# boot.net
KiCad netlist of a schematic drawn in Altium Designer
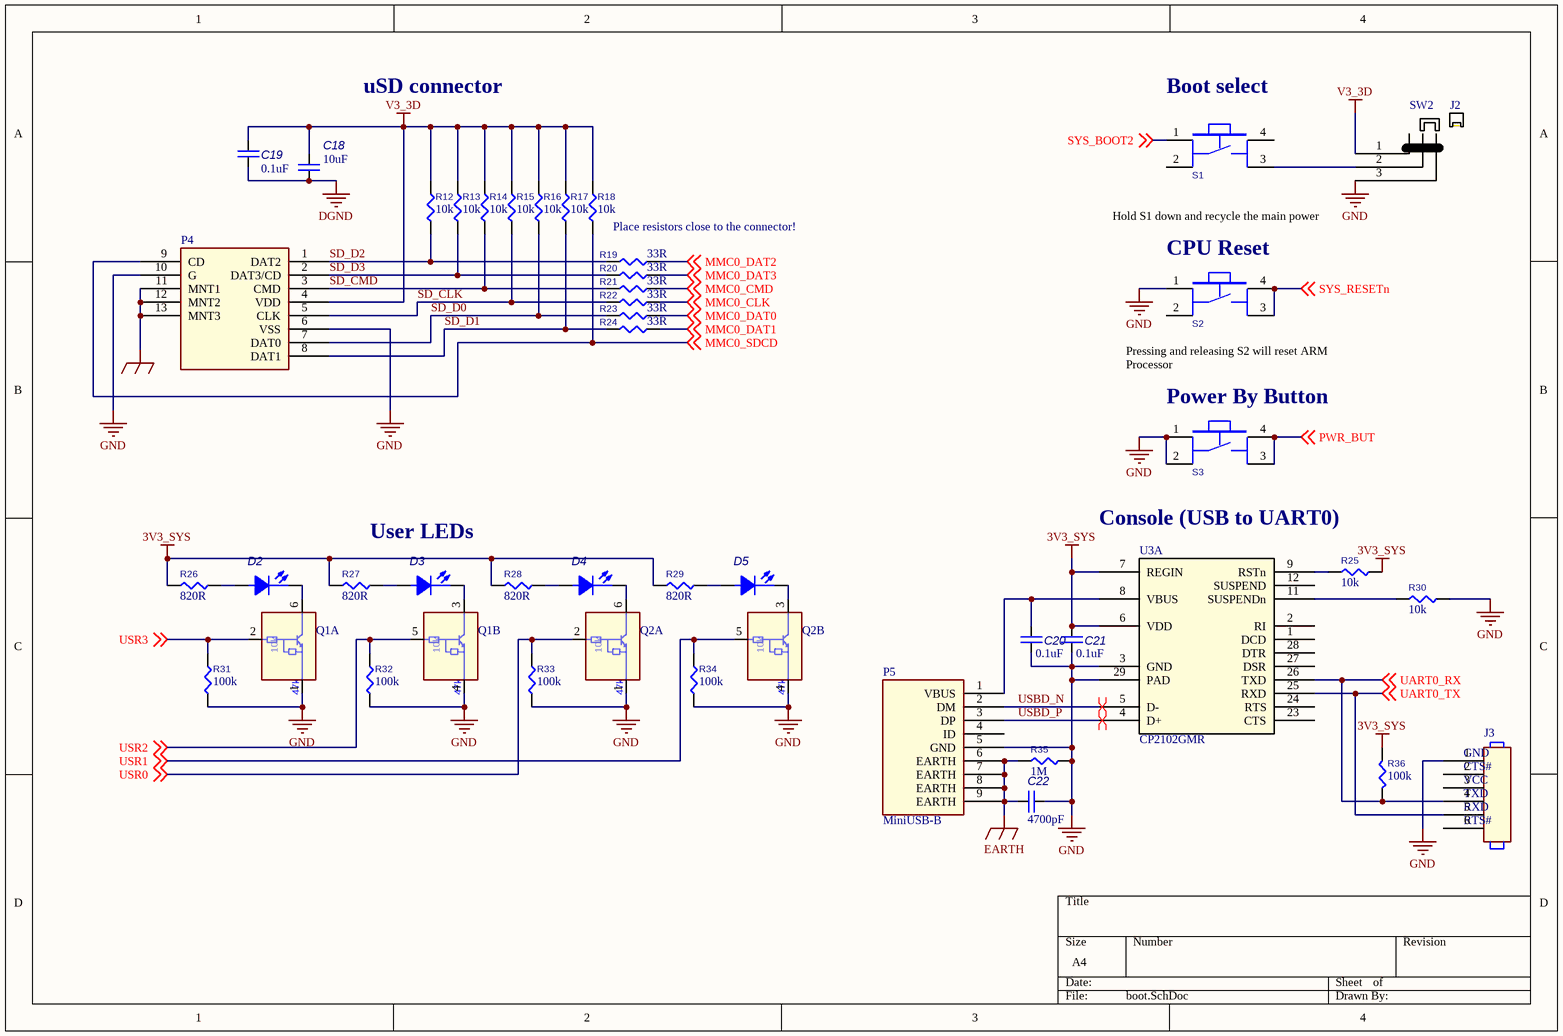
[diagram p0: boot.SchDoc]

(export (version "E")
  (design (tool "Eeschema 10.0.6"))
  (components
    (comp (ref "C18")
      (value "10uF")
      (footprint "CC2012-0805")
      (description "C0805")
      (libsource (lib "am335x-base") (part "C0805"))
    )
    (comp (ref "C19")
      (value "0.1uF")
      (footprint "CC1608-0603")
      (description "C0603")
      (libsource (lib "spider") (part "C0603"))
    )
    (comp (ref "C20")
      (value "0.1uF")
      (footprint "CC1608-0603")
      (description "C0603")
      (libsource (lib "spider") (part "C0603"))
    )
    (comp (ref "C21")
      (value "0.1uF")
      (footprint "CC1608-0603")
      (description "C0603")
      (libsource (lib "spider") (part "C0603"))
    )
    (comp (ref "C22")
      (value "4700pF")
      (footprint "CC1608-0603")
      (description "C0603")
      (libsource (lib "spider") (part "C0603"))
    )
    (comp (ref "D2")
      (value "LED0805")
      (footprint "LED0805")
      (description "LED 0805")
      (libsource (lib "spider") (part "LED0805"))
    )
    (comp (ref "D3")
      (value "LED0805")
      (footprint "LED0805")
      (description "LED 0805")
      (libsource (lib "spider") (part "LED0805"))
    )
    (comp (ref "D4")
      (value "LED0805")
      (footprint "LED0805")
      (description "LED 0805")
      (libsource (lib "spider") (part "LED0805"))
    )
    (comp (ref "D5")
      (value "LED0805")
      (footprint "LED0805")
      (description "LED 0805")
      (libsource (lib "spider") (part "LED0805"))
    )
    (comp (ref "J2")
      (value "Jumper-cap")
      (description "Jumper")
      (libsource (lib "spider") (part "Jumper-cap"))
    )
    (comp (ref "J3")
      (value "HEADER 6")
      (footprint "pls-6")
      (description "CONN HEADER 6POS, VERTICAL,  .100 STR TIN")
      (fields (field (name "MFR") "FCI"))
      (libsource (lib "spider") (part "HEADER 6"))
    )
    (comp (ref "P4")
      (value "~")
      (footprint "TFC08WP01F-A-R1K-H")
      (description "Connector for microSD™ Card (Push-push Type)")
      (fields (field (name "MFR") "AUK Contractors Co, LTD"))
      (libsource (lib "spider") (part "TFC08WP01F-R1K-H-CN"))
    )
    (comp (ref "P5")
      (value "MiniUSB-B")
      (footprint "MINI-USB-B5 SMT")
      (description "Mini USB Type B CONNECTOR")
      (fields (field (name "MFR") "Hirose"))
      (libsource (lib "spider") (part "MiniUSB-B"))
    )
    (comp (ref "Q1")
      (value "RN1907")
      (footprint "SOT363-6L")
      (description "Transistor Silicon NPN")
      (fields (field (name "MFR") "ONS"))
      (libsource (lib "spider") (part "RN1907"))
    )
    (comp (ref "Q2")
      (value "RN1907")
      (footprint "SOT363-6L")
      (description "Transistor Silicon NPN")
      (fields (field (name "MFR") "ONS"))
      (libsource (lib "spider") (part "RN1907"))
    )
    (comp (ref "R12")
      (value "10k")
      (footprint "RESC1608X55N")
      (description "R0603")
      (libsource (lib "am335x-base") (part "R0603"))
    )
    (comp (ref "R13")
      (value "10k")
      (footprint "RESC1608X55N")
      (description "R0603")
      (libsource (lib "am335x-base") (part "R0603"))
    )
    (comp (ref "R14")
      (value "10k")
      (footprint "RESC1608X55N")
      (description "R0603")
      (libsource (lib "am335x-base") (part "R0603"))
    )
    (comp (ref "R15")
      (value "10k")
      (footprint "RESC1608X55N")
      (description "R0603")
      (libsource (lib "am335x-base") (part "R0603"))
    )
    (comp (ref "R16")
      (value "10k")
      (footprint "RESC1608X55N")
      (description "R0603")
      (libsource (lib "am335x-base") (part "R0603"))
    )
    (comp (ref "R17")
      (value "10k")
      (footprint "RESC1608X55N")
      (description "R0603")
      (libsource (lib "am335x-base") (part "R0603"))
    )
    (comp (ref "R18")
      (value "10k")
      (footprint "RESC1608X55N")
      (description "R0603")
      (libsource (lib "am335x-base") (part "R0603"))
    )
    (comp (ref "R19")
      (value "33R")
      (footprint "RESC1608X55N")
      (description "R0603")
      (libsource (lib "spider") (part "R0603"))
    )
    (comp (ref "R20")
      (value "33R")
      (footprint "RESC1608X55N")
      (description "R0603")
      (libsource (lib "spider") (part "R0603"))
    )
    (comp (ref "R21")
      (value "33R")
      (footprint "RESC1608X55N")
      (description "R0603")
      (libsource (lib "spider") (part "R0603"))
    )
    (comp (ref "R22")
      (value "33R")
      (footprint "RESC1608X55N")
      (description "R0603")
      (libsource (lib "spider") (part "R0603"))
    )
    (comp (ref "R23")
      (value "33R")
      (footprint "RESC1608X55N")
      (description "R0603")
      (libsource (lib "spider") (part "R0603"))
    )
    (comp (ref "R24")
      (value "33R")
      (footprint "RESC1608X55N")
      (description "R0603")
      (libsource (lib "spider") (part "R0603"))
    )
    (comp (ref "R25")
      (value "10k")
      (footprint "RESC1608X55N")
      (description "R0603")
      (libsource (lib "spider") (part "R0603"))
    )
    (comp (ref "R26")
      (value "820R")
      (footprint "RESC1608X55N")
      (description "R0603")
      (libsource (lib "am335x-base") (part "R0603"))
    )
    (comp (ref "R27")
      (value "820R")
      (footprint "RESC1608X55N")
      (description "R0603")
      (libsource (lib "am335x-base") (part "R0603"))
    )
    (comp (ref "R28")
      (value "820R")
      (footprint "RESC1608X55N")
      (description "R0603")
      (libsource (lib "am335x-base") (part "R0603"))
    )
    (comp (ref "R29")
      (value "820R")
      (footprint "RESC1608X55N")
      (description "R0603")
      (libsource (lib "am335x-base") (part "R0603"))
    )
    (comp (ref "R30")
      (value "10k")
      (footprint "RESC1608X55N")
      (description "R0603")
      (libsource (lib "spider") (part "R0603"))
    )
    (comp (ref "R31")
      (value "100k")
      (footprint "RESC1608X55N")
      (description "R0603")
      (libsource (lib "am335x-base") (part "R0603"))
    )
    (comp (ref "R32")
      (value "100k")
      (footprint "RESC1608X55N")
      (description "R0603")
      (libsource (lib "am335x-base") (part "R0603"))
    )
    (comp (ref "R33")
      (value "100k")
      (footprint "RESC1608X55N")
      (description "R0603")
      (libsource (lib "am335x-base") (part "R0603"))
    )
    (comp (ref "R34")
      (value "100k")
      (footprint "RESC1608X55N")
      (description "R0603")
      (libsource (lib "am335x-base") (part "R0603"))
    )
    (comp (ref "R35")
      (value "1M")
      (footprint "RESC1608X55N")
      (description "R0603")
      (libsource (lib "spider") (part "R0603"))
    )
    (comp (ref "R36")
      (value "100k")
      (footprint "RESC1608X55N")
      (description "R0603")
      (libsource (lib "am335x-base") (part "R0603"))
    )
    (comp (ref "S1")
      (value "*")
      (footprint "SWT-32")
      (description "Push button")
      (libsource (lib "spider") (part "SWT-32"))
    )
    (comp (ref "S2")
      (value "*")
      (footprint "SWT-32")
      (description "Push button")
      (libsource (lib "spider") (part "SWT-32"))
    )
    (comp (ref "S3")
      (value "*")
      (footprint "SWT-32")
      (description "Push button")
      (libsource (lib "spider") (part "SWT-32"))
    )
    (comp (ref "SW2")
      (value "Jumper-3p")
      (footprint "pls-3")
      (description "PLS-3 2.54mm pin connector")
      (libsource (lib "spider") (part "Jumper-3p"))
    )
    (comp (ref "U3")
      (value "CP2102GMR")
      (footprint "Qfn28-0.5")
      (description "USB UART convertor")
      (libsource (lib "spider") (part "CP2102GMR"))
    )
  )
  (nets
    (net (code "1") (name "/SD_CLK") (class "Default")
      (node (ref "P4") (pin "5") (pinfunction "CLK_5") (pintype "passive"))
      (node (ref "R15") (pin "1") (pinfunction "1_1") (pintype "passive"))
      (node (ref "R22") (pin "1") (pinfunction "1_1") (pintype "passive"))
    )
    (net (code "2") (name "/SD_CMD") (class "Default")
      (node (ref "P4") (pin "3") (pinfunction "CMD_3") (pintype "passive"))
      (node (ref "R14") (pin "1") (pinfunction "1_1") (pintype "passive"))
      (node (ref "R21") (pin "1") (pinfunction "1_1") (pintype "passive"))
    )
    (net (code "3") (name "/SD_D0") (class "Default")
      (node (ref "P4") (pin "7") (pinfunction "DAT0_7") (pintype "passive"))
      (node (ref "R16") (pin "1") (pinfunction "1_1") (pintype "passive"))
      (node (ref "R23") (pin "1") (pinfunction "1_1") (pintype "passive"))
    )
    (net (code "4") (name "/SD_D1") (class "Default")
      (node (ref "P4") (pin "8") (pinfunction "DAT1_8") (pintype "passive"))
      (node (ref "R17") (pin "1") (pinfunction "1_1") (pintype "passive"))
      (node (ref "R24") (pin "1") (pinfunction "1_1") (pintype "passive"))
    )
    (net (code "5") (name "/SD_D2") (class "Default")
      (node (ref "P4") (pin "1") (pinfunction "DAT2_1") (pintype "passive"))
      (node (ref "R12") (pin "1") (pinfunction "1_1") (pintype "passive"))
      (node (ref "R19") (pin "1") (pinfunction "1_1") (pintype "passive"))
    )
    (net (code "6") (name "/SD_D3") (class "Default")
      (node (ref "P4") (pin "2") (pinfunction "DAT3/CD_2") (pintype "passive"))
      (node (ref "R13") (pin "1") (pinfunction "1_1") (pintype "passive"))
      (node (ref "R20") (pin "1") (pinfunction "1_1") (pintype "passive"))
    )
    (net (code "7") (name "/USBD_N") (class "Default")
      (node (ref "P5") (pin "2") (pinfunction "DM_2") (pintype "passive"))
      (node (ref "U3") (pin "5") (pinfunction "D-_5") (pintype "passive"))
    )
    (net (code "8") (name "/USBD_P") (class "Default")
      (node (ref "P5") (pin "3") (pinfunction "DP_3") (pintype "passive"))
      (node (ref "U3") (pin "4") (pinfunction "D+_4") (pintype "passive"))
    )
    (net (code "9") (name "3V3_SYS") (class "Default")
      (node (ref "C21") (pin "1") (pinfunction "1_1") (pintype "passive"))
      (node (ref "R25") (pin "2") (pinfunction "2_2") (pintype "passive"))
      (node (ref "R26") (pin "2") (pinfunction "2_2") (pintype "passive"))
      (node (ref "R27") (pin "2") (pinfunction "2_2") (pintype "passive"))
      (node (ref "R28") (pin "2") (pinfunction "2_2") (pintype "passive"))
      (node (ref "R29") (pin "2") (pinfunction "2_2") (pintype "passive"))
      (node (ref "R36") (pin "2") (pinfunction "2_2") (pintype "passive"))
      (node (ref "U3") (pin "6") (pinfunction "VDD_6") (pintype "passive"))
      (node (ref "U3") (pin "7") (pinfunction "REGIN_7") (pintype "passive"))
    )
    (net (code "10") (name "DGND") (class "Default")
      (node (ref "C18") (pin "1") (pinfunction "1_1") (pintype "passive"))
      (node (ref "C19") (pin "2") (pinfunction "2_2") (pintype "passive"))
    )
    (net (code "11") (name "EARTH") (class "Default")
      (node (ref "C22") (pin "1") (pinfunction "1_1") (pintype "passive"))
      (node (ref "P4") (pin "11") (pinfunction "MNT1_11") (pintype "passive"))
      (node (ref "P4") (pin "12") (pinfunction "MNT2_12") (pintype "passive"))
      (node (ref "P4") (pin "13") (pinfunction "MNT3_13") (pintype "passive"))
      (node (ref "P5") (pin "6") (pinfunction "EARTH_6") (pintype "passive"))
      (node (ref "P5") (pin "7") (pinfunction "EARTH_7") (pintype "passive"))
      (node (ref "P5") (pin "8") (pinfunction "EARTH_8") (pintype "passive"))
      (node (ref "P5") (pin "9") (pinfunction "EARTH_9") (pintype "passive"))
      (node (ref "R35") (pin "1") (pinfunction "1_1") (pintype "passive"))
    )
    (net (code "12") (name "GND") (class "Default")
      (node (ref "C20") (pin "2") (pinfunction "2_2") (pintype "passive"))
      (node (ref "C21") (pin "2") (pinfunction "2_2") (pintype "passive"))
      (node (ref "C22") (pin "2") (pinfunction "2_2") (pintype "passive"))
      (node (ref "J3") (pin "1") (pinfunction "1_1") (pintype "passive"))
      (node (ref "P4") (pin "10") (pinfunction "G_10") (pintype "passive"))
      (node (ref "P4") (pin "6") (pinfunction "VSS_6") (pintype "power_in"))
      (node (ref "P5") (pin "5") (pinfunction "GND_5") (pintype "power_in"))
      (node (ref "Q1") (pin "1") (pinfunction "4_1") (pintype "passive"))
      (node (ref "Q1") (pin "4") (pinfunction "4_4") (pintype "passive"))
      (node (ref "Q2") (pin "1") (pinfunction "4_1") (pintype "passive"))
      (node (ref "Q2") (pin "4") (pinfunction "4_4") (pintype "passive"))
      (node (ref "R30") (pin "2") (pinfunction "2_2") (pintype "passive"))
      (node (ref "R31") (pin "1") (pinfunction "1_1") (pintype "passive"))
      (node (ref "R32") (pin "1") (pinfunction "1_1") (pintype "passive"))
      (node (ref "R33") (pin "1") (pinfunction "1_1") (pintype "passive"))
      (node (ref "R34") (pin "1") (pinfunction "1_1") (pintype "passive"))
      (node (ref "R35") (pin "2") (pinfunction "2_2") (pintype "passive"))
      (node (ref "S2") (pin "1") (pintype "passive"))
      (node (ref "S3") (pin "1") (pintype "passive"))
      (node (ref "S3") (pin "2") (pintype "passive"))
      (node (ref "SW2") (pin "3") (pinfunction "3_3") (pintype "passive"))
      (node (ref "U3") (pin "29") (pinfunction "PAD_29") (pintype "passive"))
      (node (ref "U3") (pin "3") (pinfunction "GND_3") (pintype "passive"))
    )
    (net (code "13") (name "MMC0_CLK") (class "Default")
      (node (ref "R22") (pin "2") (pinfunction "2_2") (pintype "passive"))
    )
    (net (code "14") (name "MMC0_CMD") (class "Default")
      (node (ref "R21") (pin "2") (pinfunction "2_2") (pintype "passive"))
    )
    (net (code "15") (name "MMC0_DAT0") (class "Default")
      (node (ref "R23") (pin "2") (pinfunction "2_2") (pintype "passive"))
    )
    (net (code "16") (name "MMC0_DAT1") (class "Default")
      (node (ref "R24") (pin "2") (pinfunction "2_2") (pintype "passive"))
    )
    (net (code "17") (name "MMC0_DAT2") (class "Default")
      (node (ref "R19") (pin "2") (pinfunction "2_2") (pintype "passive"))
    )
    (net (code "18") (name "MMC0_DAT3") (class "Default")
      (node (ref "R20") (pin "2") (pinfunction "2_2") (pintype "passive"))
    )
    (net (code "19") (name "MMC0_SDCD") (class "Default")
      (node (ref "P4") (pin "9") (pinfunction "CD_9") (pintype "passive"))
      (node (ref "R18") (pin "1") (pinfunction "1_1") (pintype "passive"))
    )
    (net (code "20") (name "Net-(D2-C)") (class "Default")
      (node (ref "D2") (pin "K") (pinfunction "C_K") (pintype "passive"))
      (node (ref "Q1") (pin "6") (pinfunction "3_6") (pintype "passive"))
    )
    (net (code "21") (name "Net-(D2-PadA)") (class "Default")
      (node (ref "D2") (pin "A") (pinfunction "A_A") (pintype "passive"))
      (node (ref "R26") (pin "1") (pinfunction "1_1") (pintype "passive"))
    )
    (net (code "22") (name "Net-(D3-C)") (class "Default")
      (node (ref "D3") (pin "K") (pinfunction "C_K") (pintype "passive"))
      (node (ref "Q1") (pin "3") (pinfunction "3_3") (pintype "passive"))
    )
    (net (code "23") (name "Net-(D3-PadA)") (class "Default")
      (node (ref "D3") (pin "A") (pinfunction "A_A") (pintype "passive"))
      (node (ref "R27") (pin "1") (pinfunction "1_1") (pintype "passive"))
    )
    (net (code "24") (name "Net-(D4-C)") (class "Default")
      (node (ref "D4") (pin "K") (pinfunction "C_K") (pintype "passive"))
      (node (ref "Q2") (pin "6") (pinfunction "3_6") (pintype "passive"))
    )
    (net (code "25") (name "Net-(D4-PadA)") (class "Default")
      (node (ref "D4") (pin "A") (pinfunction "A_A") (pintype "passive"))
      (node (ref "R28") (pin "1") (pinfunction "1_1") (pintype "passive"))
    )
    (net (code "26") (name "Net-(D5-C)") (class "Default")
      (node (ref "D5") (pin "K") (pinfunction "C_K") (pintype "passive"))
      (node (ref "Q2") (pin "3") (pinfunction "3_3") (pintype "passive"))
    )
    (net (code "27") (name "Net-(D5-PadA)") (class "Default")
      (node (ref "D5") (pin "A") (pinfunction "A_A") (pintype "passive"))
      (node (ref "R29") (pin "1") (pinfunction "1_1") (pintype "passive"))
    )
    (net (code "28") (name "Net-(P5-VBUS)") (class "Default")
      (node (ref "C20") (pin "1") (pinfunction "1_1") (pintype "passive"))
      (node (ref "P5") (pin "1") (pinfunction "VBUS_1") (pintype "power_in"))
      (node (ref "U3") (pin "8") (pinfunction "VBUS_8") (pintype "passive"))
    )
    (net (code "29") (name "Net-(S1-Pad3)") (class "Default")
      (node (ref "S1") (pin "3") (pintype "passive"))
      (node (ref "SW2") (pin "2") (pinfunction "2_2") (pintype "passive"))
    )
    (net (code "30") (name "Net-(U3A-RSTn)") (class "Default")
      (node (ref "R25") (pin "1") (pinfunction "1_1") (pintype "passive"))
      (node (ref "U3") (pin "9") (pinfunction "RSTn_9") (pintype "passive"))
    )
    (net (code "31") (name "Net-(U3A-SUSPENDn)") (class "Default")
      (node (ref "R30") (pin "1") (pinfunction "1_1") (pintype "passive"))
      (node (ref "U3") (pin "11") (pinfunction "SUSPENDn_11") (pintype "passive"))
    )
    (net (code "32") (name "PWR_BUT") (class "Default")
      (node (ref "S3") (pin "3") (pintype "passive"))
      (node (ref "S3") (pin "4") (pintype "passive"))
    )
    (net (code "33") (name "SYS_BOOT2") (class "Default") (node (ref "S1") (pin "1") (pintype "passive")))
    (net (code "34") (name "SYS_RESETn") (class "Default")
      (node (ref "S2") (pin "3") (pintype "passive"))
      (node (ref "S2") (pin "4") (pintype "passive"))
    )
    (net (code "35") (name "UART0_RX") (class "Default")
      (node (ref "J3") (pin "4") (pinfunction "4_4") (pintype "passive"))
      (node (ref "R36") (pin "1") (pinfunction "1_1") (pintype "passive"))
      (node (ref "U3") (pin "26") (pinfunction "TXD_26") (pintype "passive"))
    )
    (net (code "36") (name "UART0_TX") (class "Default")
      (node (ref "J3") (pin "5") (pinfunction "5_5") (pintype "passive"))
      (node (ref "U3") (pin "25") (pinfunction "RXD_25") (pintype "passive"))
    )
    (net (code "37") (name "USR0") (class "Default")
      (node (ref "Q2") (pin "2") (pinfunction "5_2") (pintype "passive"))
      (node (ref "R33") (pin "2") (pinfunction "2_2") (pintype "passive"))
    )
    (net (code "38") (name "USR1") (class "Default")
      (node (ref "Q2") (pin "5") (pinfunction "5_5") (pintype "passive"))
      (node (ref "R34") (pin "2") (pinfunction "2_2") (pintype "passive"))
    )
    (net (code "39") (name "USR2") (class "Default")
      (node (ref "Q1") (pin "5") (pinfunction "5_5") (pintype "passive"))
      (node (ref "R32") (pin "2") (pinfunction "2_2") (pintype "passive"))
    )
    (net (code "40") (name "USR3") (class "Default")
      (node (ref "Q1") (pin "2") (pinfunction "5_2") (pintype "passive"))
      (node (ref "R31") (pin "2") (pinfunction "2_2") (pintype "passive"))
    )
    (net (code "41") (name "V3_3D") (class "Default")
      (node (ref "C18") (pin "2") (pinfunction "2_2") (pintype "passive"))
      (node (ref "C19") (pin "1") (pinfunction "1_1") (pintype "passive"))
      (node (ref "P4") (pin "4") (pinfunction "VDD_4") (pintype "power_in"))
      (node (ref "R12") (pin "2") (pinfunction "2_2") (pintype "passive"))
      (node (ref "R13") (pin "2") (pinfunction "2_2") (pintype "passive"))
      (node (ref "R14") (pin "2") (pinfunction "2_2") (pintype "passive"))
      (node (ref "R15") (pin "2") (pinfunction "2_2") (pintype "passive"))
      (node (ref "R16") (pin "2") (pinfunction "2_2") (pintype "passive"))
      (node (ref "R17") (pin "2") (pinfunction "2_2") (pintype "passive"))
      (node (ref "R18") (pin "2") (pinfunction "2_2") (pintype "passive"))
      (node (ref "SW2") (pin "1") (pinfunction "1_1") (pintype "passive"))
    )
    (net (code "42") (name "unconnected-(J3-Pad2)") (class "Default")
      (node (ref "J3") (pin "2") (pinfunction "2_2") (pintype "passive"))
    )
    (net (code "43") (name "unconnected-(J3-Pad3)") (class "Default")
      (node (ref "J3") (pin "3") (pinfunction "3_3") (pintype "passive"))
    )
    (net (code "44") (name "unconnected-(J3-Pad6)") (class "Default")
      (node (ref "J3") (pin "6") (pinfunction "6_6") (pintype "passive"))
    )
    (net (code "45") (name "unconnected-(P5-ID-Pad4)") (class "Default")
      (node (ref "P5") (pin "4") (pinfunction "ID_4") (pintype "passive"))
    )
    (net (code "46") (name "unconnected-(S1-Pad2)") (class "Default")
      (node (ref "S1") (pin "2") (pintype "passive"))
    )
    (net (code "47") (name "unconnected-(S1-Pad4)") (class "Default")
      (node (ref "S1") (pin "4") (pintype "passive"))
    )
    (net (code "48") (name "unconnected-(S2-Pad2)") (class "Default")
      (node (ref "S2") (pin "2") (pintype "passive"))
    )
    (net (code "49") (name "unconnected-(U3A-CTS-Pad23)") (class "Default")
      (node (ref "U3") (pin "23") (pinfunction "CTS_23") (pintype "passive"))
    )
    (net (code "50") (name "unconnected-(U3A-DCD-Pad1)") (class "Default")
      (node (ref "U3") (pin "1") (pinfunction "DCD_1") (pintype "passive"))
    )
    (net (code "51") (name "unconnected-(U3A-DSR-Pad27)") (class "Default")
      (node (ref "U3") (pin "27") (pinfunction "DSR_27") (pintype "passive"))
    )
    (net (code "52") (name "unconnected-(U3A-DTR-Pad28)") (class "Default")
      (node (ref "U3") (pin "28") (pinfunction "DTR_28") (pintype "passive"))
    )
    (net (code "53") (name "unconnected-(U3A-RI-Pad2)") (class "Default")
      (node (ref "U3") (pin "2") (pinfunction "RI_2") (pintype "passive"))
    )
    (net (code "54") (name "unconnected-(U3A-RTS-Pad24)") (class "Default")
      (node (ref "U3") (pin "24") (pinfunction "RTS_24") (pintype "passive"))
    )
    (net (code "55") (name "unconnected-(U3A-SUSPEND-Pad12)") (class "Default")
      (node (ref "U3") (pin "12") (pinfunction "SUSPEND_12") (pintype "passive"))
    )
  )
)
